# Clock_Schematic_v_2.net
KiCad netlist of a schematic drawn in EAGLE
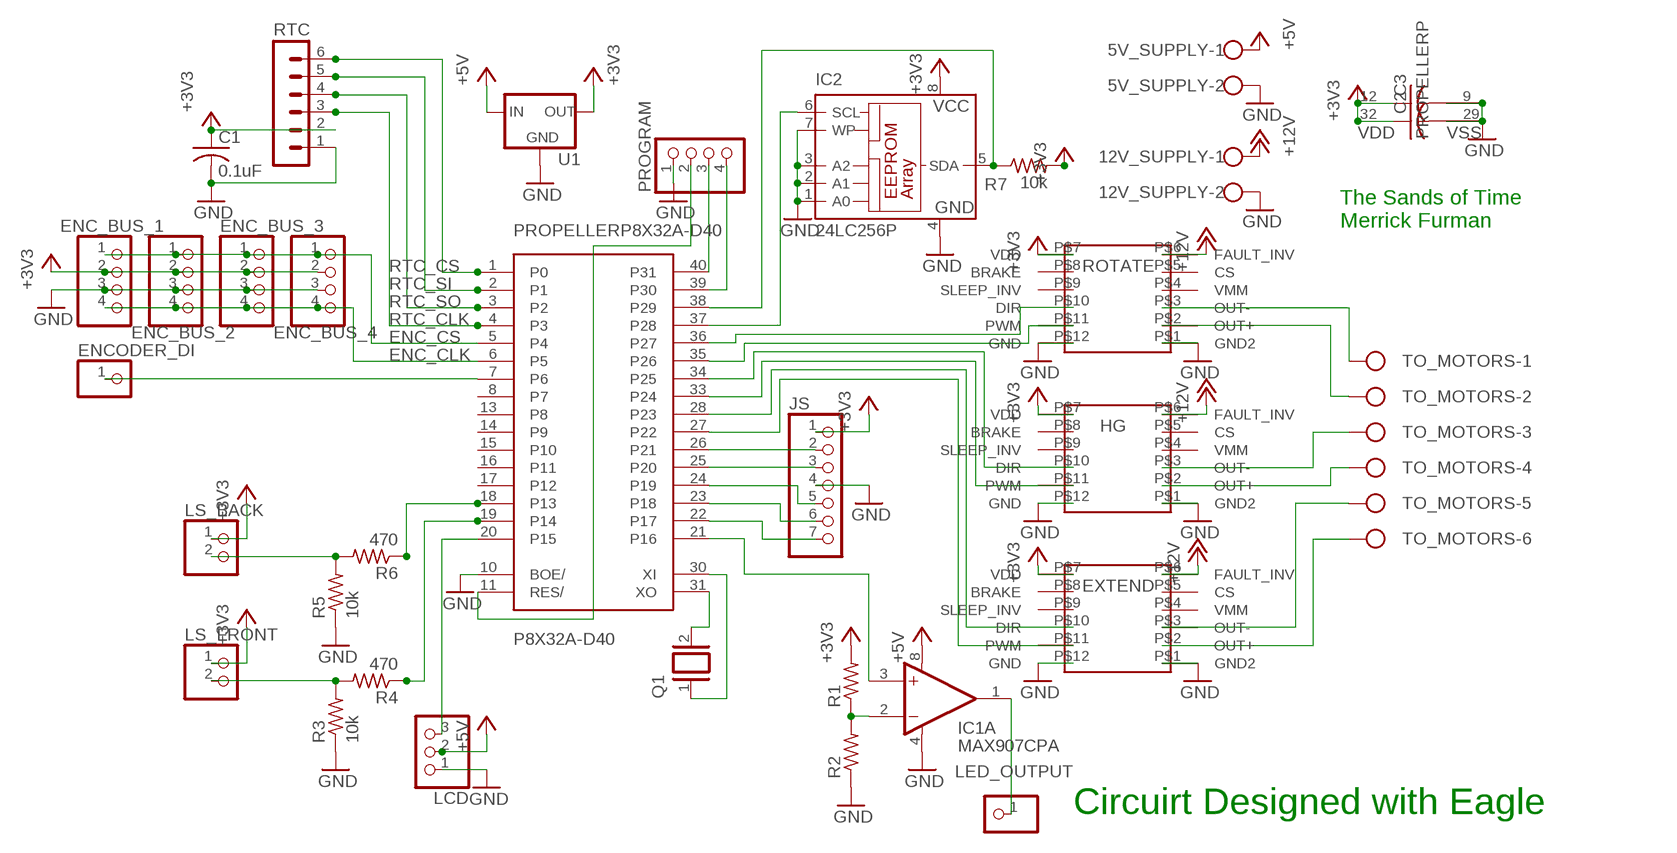
[diagram p0: schematic, sheet 1]

(export (version "E")
  (design (tool "Eeschema 10.0.6"))
  (components
    (comp (ref "5V_SUPPLY")
      (value "W237-102")
      (footprint "eagle-import:W237-102")
      (fields (field (name "MPN") "237-102"))
      (libsource (lib "eagle-import") (part "W237-102"))
    )
    (comp (ref "12V_SUPPLY")
      (value "W237-102")
      (footprint "eagle-import:W237-102")
      (fields (field (name "MPN") "237-102"))
      (libsource (lib "eagle-import") (part "W237-102"))
    )
    (comp (ref "C1")
      (value "0.1uF")
      (footprint "eagle-import:C050-025X075")
      (libsource (lib "eagle-import") (part "C-US050-025X075"))
    )
    (comp (ref "C2")
      (value "C-US050-025X075")
      (footprint "eagle-import:C050-025X075")
      (libsource (lib "eagle-import") (part "C-US050-025X075"))
    )
    (comp (ref "C3")
      (value "C-US050-025X075")
      (footprint "eagle-import:C050-025X075")
      (libsource (lib "eagle-import") (part "C-US050-025X075"))
    )
    (comp (ref "ENCODER_DI")
      (value "PINHD-1X1")
      (footprint "eagle-import:1X01")
      (libsource (lib "eagle-import") (part "PINHD-1X1"))
    )
    (comp (ref "ENC_BUS_1")
      (value "PINHD-1X4")
      (footprint "eagle-import:1X04")
      (libsource (lib "eagle-import") (part "PINHD-1X4"))
    )
    (comp (ref "ENC_BUS_2")
      (value "PINHD-1X4")
      (footprint "eagle-import:1X04")
      (libsource (lib "eagle-import") (part "PINHD-1X4"))
    )
    (comp (ref "ENC_BUS_3")
      (value "PINHD-1X4")
      (footprint "eagle-import:1X04")
      (libsource (lib "eagle-import") (part "PINHD-1X4"))
    )
    (comp (ref "ENC_BUS_4")
      (value "PINHD-1X4")
      (footprint "eagle-import:1X04")
      (libsource (lib "eagle-import") (part "PINHD-1X4"))
    )
    (comp (ref "EXTEND")
      (value "DRV")
      (footprint "eagle-import:DRV")
      (libsource (lib "eagle-import") (part "DRV"))
    )
    (comp (ref "HG")
      (value "DRV")
      (footprint "eagle-import:DRV")
      (libsource (lib "eagle-import") (part "DRV"))
    )
    (comp (ref "IC1")
      (value "MAX907CPA")
      (footprint "eagle-import:DIL08")
      (fields (field (name "MF") "MAXIM"))
      (libsource (lib "eagle-import") (part "MAX907CPA"))
    )
    (comp (ref "IC2")
      (value "24LC256P")
      (footprint "eagle-import:DIL8")
      (fields (field (name "MF") "MICROCHIP") (field (name "MPN") "24LC256-E/P"))
      (libsource (lib "eagle-import") (part "24PLC256"))
    )
    (comp (ref "JS")
      (value "PINHD-1X7")
      (footprint "eagle-import:1X07")
      (libsource (lib "eagle-import") (part "PINHD-1X7"))
    )
    (comp (ref "LCD")
      (value "PINHD-1X3")
      (footprint "eagle-import:1X03")
      (libsource (lib "eagle-import") (part "PINHD-1X3"))
    )
    (comp (ref "LED_OUTPUT")
      (value "PINHD-1X1")
      (footprint "eagle-import:1X01")
      (libsource (lib "eagle-import") (part "PINHD-1X1"))
    )
    (comp (ref "LS_BACK")
      (value "PINHD-1X2")
      (footprint "eagle-import:1X02")
      (libsource (lib "eagle-import") (part "PINHD-1X2"))
    )
    (comp (ref "LS_FRONT")
      (value "PINHD-1X2")
      (footprint "eagle-import:1X02")
      (libsource (lib "eagle-import") (part "PINHD-1X2"))
    )
    (comp (ref "PROGRAM")
      (value "PINHD-1X4")
      (footprint "eagle-import:1X04")
      (libsource (lib "eagle-import") (part "PINHD-1X4"))
    )
    (comp (ref "PROPELLER")
      (value "P8X32A-D40")
      (footprint "eagle-import:P8X32A-D40")
      (libsource (lib "eagle-import") (part "P8X32A-D40"))
    )
    (comp (ref "Q1")
      (value "XTAL/S")
      (footprint "eagle-import:QS")
      (libsource (lib "eagle-import") (part "XTAL/S"))
    )
    (comp (ref "R1")
      (value "R-US_0207/10")
      (footprint "eagle-import:0207_10")
      (libsource (lib "eagle-import") (part "R-US_0207/10"))
    )
    (comp (ref "R2")
      (value "R-US_0207/10")
      (footprint "eagle-import:0207_10")
      (libsource (lib "eagle-import") (part "R-US_0207/10"))
    )
    (comp (ref "R3")
      (value "10k")
      (footprint "eagle-import:0207_10")
      (libsource (lib "eagle-import") (part "R-US_0207/10"))
    )
    (comp (ref "R4")
      (value "470")
      (footprint "eagle-import:0207_10")
      (libsource (lib "eagle-import") (part "R-US_0207/10"))
    )
    (comp (ref "R5")
      (value "10k")
      (footprint "eagle-import:0207_10")
      (libsource (lib "eagle-import") (part "R-US_0207/10"))
    )
    (comp (ref "R6")
      (value "470")
      (footprint "eagle-import:0207_10")
      (libsource (lib "eagle-import") (part "R-US_0207/10"))
    )
    (comp (ref "R7")
      (value "10k")
      (footprint "eagle-import:0207_10")
      (libsource (lib "eagle-import") (part "R-US_0207/10"))
    )
    (comp (ref "ROTATE")
      (value "DRV")
      (footprint "eagle-import:DRV")
      (libsource (lib "eagle-import") (part "DRV"))
    )
    (comp (ref "RTC")
      (value "MA06-1")
      (footprint "eagle-import:MA06-1")
      (libsource (lib "eagle-import") (part "MA06-1"))
    )
    (comp (ref "TO_MOTORS")
      (value "W237-6")
      (footprint "eagle-import:W237-6")
      (libsource (lib "eagle-import") (part "W237-6"))
    )
    (comp (ref "U1")
      (value "V_REG_78XXSIDE")
      (footprint "eagle-import:78XXL")
      (libsource (lib "eagle-import") (part "V_REG_78XXSIDE"))
    )
  )
  (nets
    (net (code "1") (name "+3V3") (class "Default")
      (node (ref "C1") (pin "1") (pinfunction "1_1") (pintype "passive"))
      (node (ref "C2") (pin "1") (pinfunction "1_1") (pintype "passive"))
      (node (ref "C3") (pin "1") (pinfunction "1_1") (pintype "passive"))
      (node (ref "ENC_BUS_1") (pin "2") (pinfunction "2_2") (pintype "passive"))
      (node (ref "ENC_BUS_2") (pin "2") (pinfunction "2_2") (pintype "passive"))
      (node (ref "ENC_BUS_3") (pin "2") (pinfunction "2_2") (pintype "passive"))
      (node (ref "ENC_BUS_4") (pin "2") (pinfunction "2_2") (pintype "passive"))
      (node (ref "EXTEND") (pin "P$7") (pinfunction "VDD_P$7") (pintype "bidirectional"))
      (node (ref "HG") (pin "P$7") (pinfunction "VDD_P$7") (pintype "bidirectional"))
      (node (ref "IC2") (pin "8") (pinfunction "VCC_8") (pintype "power_in"))
      (node (ref "JS") (pin "1") (pinfunction "1_1") (pintype "passive"))
      (node (ref "LS_BACK") (pin "1") (pinfunction "1_1") (pintype "passive"))
      (node (ref "LS_FRONT") (pin "1") (pinfunction "1_1") (pintype "passive"))
      (node (ref "PROPELLER") (pin "12") (pinfunction "VDD_12") (pintype "power_in"))
      (node (ref "PROPELLER") (pin "32") (pinfunction "VDD_32") (pintype "power_in"))
      (node (ref "R1") (pin "2") (pinfunction "2_2") (pintype "passive"))
      (node (ref "R7") (pin "2") (pinfunction "2_2") (pintype "passive"))
      (node (ref "ROTATE") (pin "P$7") (pinfunction "VDD_P$7") (pintype "bidirectional"))
      (node (ref "RTC") (pin "2") (pinfunction "2_2") (pintype "passive"))
      (node (ref "U1") (pin "OUT") (pinfunction "OUT_OUT") (pintype "passive"))
    )
    (net (code "2") (name "+5V") (class "Default")
      (node (ref "5V_SUPPLY") (pin "1") (pinfunction "KL_1") (pintype "passive"))
      (node (ref "IC1") (pin "8") (pinfunction "V+_8") (pintype "power_in"))
      (node (ref "LCD") (pin "2") (pinfunction "2_2") (pintype "passive"))
      (node (ref "U1") (pin "IN") (pinfunction "IN_IN") (pintype "input"))
    )
    (net (code "3") (name "+12V") (class "Default")
      (node (ref "12V_SUPPLY") (pin "1") (pinfunction "KL_1") (pintype "passive"))
      (node (ref "EXTEND") (pin "P$6") (pinfunction "FAULT_INV_P$6") (pintype "bidirectional"))
      (node (ref "HG") (pin "P$6") (pinfunction "FAULT_INV_P$6") (pintype "bidirectional"))
      (node (ref "ROTATE") (pin "P$6") (pinfunction "FAULT_INV_P$6") (pintype "bidirectional"))
    )
    (net (code "4") (name "/ENC_CLK") (class "Default")
      (node (ref "ENC_BUS_1") (pin "4") (pinfunction "4_4") (pintype "passive"))
      (node (ref "ENC_BUS_2") (pin "4") (pinfunction "4_4") (pintype "passive"))
      (node (ref "ENC_BUS_3") (pin "4") (pinfunction "4_4") (pintype "passive"))
      (node (ref "ENC_BUS_4") (pin "4") (pinfunction "4_4") (pintype "passive"))
      (node (ref "PROPELLER") (pin "6") (pinfunction "P5_6") (pintype "bidirectional"))
    )
    (net (code "5") (name "/ENC_CS") (class "Default")
      (node (ref "ENC_BUS_1") (pin "1") (pinfunction "1_1") (pintype "passive"))
      (node (ref "ENC_BUS_2") (pin "1") (pinfunction "1_1") (pintype "passive"))
      (node (ref "ENC_BUS_3") (pin "1") (pinfunction "1_1") (pintype "passive"))
      (node (ref "ENC_BUS_4") (pin "1") (pinfunction "1_1") (pintype "passive"))
      (node (ref "PROPELLER") (pin "5") (pinfunction "P4_5") (pintype "bidirectional"))
    )
    (net (code "6") (name "/RTC_CLK") (class "Default")
      (node (ref "PROPELLER") (pin "4") (pinfunction "P3_4") (pintype "bidirectional"))
      (node (ref "RTC") (pin "3") (pinfunction "3_3") (pintype "passive"))
    )
    (net (code "7") (name "/RTC_CS") (class "Default")
      (node (ref "PROPELLER") (pin "1") (pinfunction "P0_1") (pintype "bidirectional"))
      (node (ref "RTC") (pin "6") (pinfunction "6_6") (pintype "passive"))
    )
    (net (code "8") (name "/RTC_SI") (class "Default")
      (node (ref "PROPELLER") (pin "2") (pinfunction "P1_2") (pintype "bidirectional"))
      (node (ref "RTC") (pin "5") (pinfunction "5_5") (pintype "passive"))
    )
    (net (code "9") (name "/RTC_SO") (class "Default")
      (node (ref "PROPELLER") (pin "3") (pinfunction "P2_3") (pintype "bidirectional"))
      (node (ref "RTC") (pin "4") (pinfunction "4_4") (pintype "passive"))
    )
    (net (code "10") (name "GND") (class "Default")
      (node (ref "12V_SUPPLY") (pin "2") (pinfunction "KL_2") (pintype "passive"))
      (node (ref "5V_SUPPLY") (pin "2") (pinfunction "KL_2") (pintype "passive"))
      (node (ref "C1") (pin "2") (pinfunction "2_2") (pintype "passive"))
      (node (ref "C2") (pin "2") (pinfunction "2_2") (pintype "passive"))
      (node (ref "C3") (pin "2") (pinfunction "2_2") (pintype "passive"))
      (node (ref "ENC_BUS_1") (pin "3") (pinfunction "3_3") (pintype "passive"))
      (node (ref "ENC_BUS_2") (pin "3") (pinfunction "3_3") (pintype "passive"))
      (node (ref "ENC_BUS_3") (pin "3") (pinfunction "3_3") (pintype "passive"))
      (node (ref "ENC_BUS_4") (pin "3") (pinfunction "3_3") (pintype "passive"))
      (node (ref "EXTEND") (pin "P$1") (pinfunction "GND2_P$1") (pintype "bidirectional"))
      (node (ref "EXTEND") (pin "P$12") (pinfunction "GND_P$12") (pintype "bidirectional"))
      (node (ref "HG") (pin "P$1") (pinfunction "GND2_P$1") (pintype "bidirectional"))
      (node (ref "HG") (pin "P$12") (pinfunction "GND_P$12") (pintype "bidirectional"))
      (node (ref "IC1") (pin "4") (pinfunction "V-_4") (pintype "power_in"))
      (node (ref "IC2") (pin "1") (pinfunction "A0_1") (pintype "input"))
      (node (ref "IC2") (pin "2") (pinfunction "A1_2") (pintype "input"))
      (node (ref "IC2") (pin "3") (pinfunction "A2_3") (pintype "input"))
      (node (ref "IC2") (pin "4") (pinfunction "GND_4") (pintype "power_in"))
      (node (ref "IC2") (pin "7") (pinfunction "WP_7") (pintype "input"))
      (node (ref "JS") (pin "4") (pinfunction "4_4") (pintype "passive"))
      (node (ref "LCD") (pin "1") (pinfunction "1_1") (pintype "passive"))
      (node (ref "PROGRAM") (pin "1") (pinfunction "1_1") (pintype "passive"))
      (node (ref "PROPELLER") (pin "10") (pinfunction "BOE/_10") (pintype "input"))
      (node (ref "PROPELLER") (pin "29") (pinfunction "VSS_29") (pintype "power_in"))
      (node (ref "PROPELLER") (pin "9") (pinfunction "VSS_9") (pintype "power_in"))
      (node (ref "R2") (pin "1") (pinfunction "1_1") (pintype "passive"))
      (node (ref "R3") (pin "1") (pinfunction "1_1") (pintype "passive"))
      (node (ref "R5") (pin "1") (pinfunction "1_1") (pintype "passive"))
      (node (ref "ROTATE") (pin "P$1") (pinfunction "GND2_P$1") (pintype "bidirectional"))
      (node (ref "ROTATE") (pin "P$12") (pinfunction "GND_P$12") (pintype "bidirectional"))
      (node (ref "RTC") (pin "1") (pinfunction "1_1") (pintype "passive"))
      (node (ref "U1") (pin "GND") (pinfunction "GND_GND") (pintype "input"))
    )
    (net (code "11") (name "Net-(EXTEND-DIR)") (class "Default")
      (node (ref "EXTEND") (pin "P$10") (pinfunction "DIR_P$10") (pintype "bidirectional"))
      (node (ref "PROPELLER") (pin "28") (pinfunction "P23_28") (pintype "bidirectional"))
    )
    (net (code "12") (name "Net-(EXTEND-OUT+)") (class "Default")
      (node (ref "EXTEND") (pin "P$2") (pinfunction "OUT+_P$2") (pintype "bidirectional"))
      (node (ref "TO_MOTORS") (pin "6") (pinfunction "KL_6") (pintype "passive"))
    )
    (net (code "13") (name "Net-(EXTEND-OUT-)") (class "Default")
      (node (ref "EXTEND") (pin "P$3") (pinfunction "OUT-_P$3") (pintype "bidirectional"))
      (node (ref "TO_MOTORS") (pin "5") (pinfunction "KL_5") (pintype "passive"))
    )
    (net (code "14") (name "Net-(EXTEND-PWM)") (class "Default")
      (node (ref "EXTEND") (pin "P$11") (pinfunction "PWM_P$11") (pintype "bidirectional"))
      (node (ref "PROPELLER") (pin "27") (pinfunction "P22_27") (pintype "bidirectional"))
    )
    (net (code "15") (name "Net-(HG-DIR)") (class "Default")
      (node (ref "HG") (pin "P$10") (pinfunction "DIR_P$10") (pintype "bidirectional"))
      (node (ref "PROPELLER") (pin "34") (pinfunction "P25_34") (pintype "bidirectional"))
    )
    (net (code "16") (name "Net-(HG-OUT+)") (class "Default")
      (node (ref "HG") (pin "P$2") (pinfunction "OUT+_P$2") (pintype "bidirectional"))
      (node (ref "TO_MOTORS") (pin "4") (pinfunction "KL_4") (pintype "passive"))
    )
    (net (code "17") (name "Net-(HG-OUT-)") (class "Default")
      (node (ref "HG") (pin "P$3") (pinfunction "OUT-_P$3") (pintype "bidirectional"))
      (node (ref "TO_MOTORS") (pin "3") (pinfunction "KL_3") (pintype "passive"))
    )
    (net (code "18") (name "Net-(HG-PWM)") (class "Default")
      (node (ref "HG") (pin "P$11") (pinfunction "PWM_P$11") (pintype "bidirectional"))
      (node (ref "PROPELLER") (pin "33") (pinfunction "P24_33") (pintype "bidirectional"))
    )
    (net (code "19") (name "Net-(IC1A-+IN)") (class "Default")
      (node (ref "IC1") (pin "3") (pinfunction "+IN_3") (pintype "input"))
      (node (ref "PROPELLER") (pin "21") (pinfunction "P16_21") (pintype "bidirectional"))
    )
    (net (code "20") (name "Net-(IC1A--IN)") (class "Default")
      (node (ref "IC1") (pin "2") (pinfunction "-IN_2") (pintype "input"))
      (node (ref "R1") (pin "1") (pinfunction "1_1") (pintype "passive"))
      (node (ref "R2") (pin "2") (pinfunction "2_2") (pintype "passive"))
    )
    (net (code "21") (name "Net-(IC1A-OUT)") (class "Default")
      (node (ref "IC1") (pin "1") (pinfunction "OUT_1") (pintype "output"))
      (node (ref "LED_OUTPUT") (pin "1") (pinfunction "1_1") (pintype "passive"))
    )
    (net (code "22") (name "Net-(IC2-SCL)") (class "Default")
      (node (ref "IC2") (pin "6") (pinfunction "SCL_6") (pintype "input"))
      (node (ref "PROPELLER") (pin "37") (pinfunction "P28_37") (pintype "bidirectional"))
    )
    (net (code "23") (name "Net-(IC2-SDA)") (class "Default")
      (node (ref "IC2") (pin "5") (pinfunction "SDA_5") (pintype "bidirectional"))
      (node (ref "PROPELLER") (pin "38") (pinfunction "P29_38") (pintype "bidirectional"))
      (node (ref "R7") (pin "1") (pinfunction "1_1") (pintype "passive"))
    )
    (net (code "24") (name "Net-(LS_BACK-Pad2)") (class "Default")
      (node (ref "LS_BACK") (pin "2") (pinfunction "2_2") (pintype "passive"))
      (node (ref "R5") (pin "2") (pinfunction "2_2") (pintype "passive"))
      (node (ref "R6") (pin "2") (pinfunction "2_2") (pintype "passive"))
    )
    (net (code "25") (name "Net-(LS_FRONT-Pad2)") (class "Default")
      (node (ref "LS_FRONT") (pin "2") (pinfunction "2_2") (pintype "passive"))
      (node (ref "R3") (pin "2") (pinfunction "2_2") (pintype "passive"))
      (node (ref "R4") (pin "2") (pinfunction "2_2") (pintype "passive"))
    )
    (net (code "26") (name "Net-(PROPELLERB-P6)") (class "Default")
      (node (ref "ENCODER_DI") (pin "1") (pinfunction "1_1") (pintype "passive"))
      (node (ref "PROPELLER") (pin "7") (pinfunction "P6_7") (pintype "bidirectional"))
    )
    (net (code "27") (name "Net-(PROPELLERB-P13)") (class "Default")
      (node (ref "PROPELLER") (pin "18") (pinfunction "P13_18") (pintype "bidirectional"))
      (node (ref "R6") (pin "1") (pinfunction "1_1") (pintype "passive"))
    )
    (net (code "28") (name "Net-(PROPELLERB-P14)") (class "Default")
      (node (ref "PROPELLER") (pin "19") (pinfunction "P14_19") (pintype "bidirectional"))
      (node (ref "R4") (pin "1") (pinfunction "1_1") (pintype "passive"))
    )
    (net (code "29") (name "Net-(PROPELLERB-P15)") (class "Default")
      (node (ref "LCD") (pin "3") (pinfunction "3_3") (pintype "passive"))
      (node (ref "PROPELLER") (pin "20") (pinfunction "P15_20") (pintype "bidirectional"))
    )
    (net (code "30") (name "Net-(PROPELLERB-P17)") (class "Default")
      (node (ref "JS") (pin "7") (pinfunction "7_7") (pintype "passive"))
      (node (ref "PROPELLER") (pin "22") (pinfunction "P17_22") (pintype "bidirectional"))
    )
    (net (code "31") (name "Net-(PROPELLERB-P18)") (class "Default")
      (node (ref "JS") (pin "6") (pinfunction "6_6") (pintype "passive"))
      (node (ref "PROPELLER") (pin "23") (pinfunction "P18_23") (pintype "bidirectional"))
    )
    (net (code "32") (name "Net-(PROPELLERB-P19)") (class "Default")
      (node (ref "JS") (pin "5") (pinfunction "5_5") (pintype "passive"))
      (node (ref "PROPELLER") (pin "24") (pinfunction "P19_24") (pintype "bidirectional"))
    )
    (net (code "33") (name "Net-(PROPELLERB-P20)") (class "Default")
      (node (ref "JS") (pin "3") (pinfunction "3_3") (pintype "passive"))
      (node (ref "PROPELLER") (pin "25") (pinfunction "P20_25") (pintype "bidirectional"))
    )
    (net (code "34") (name "Net-(PROPELLERB-P21)") (class "Default")
      (node (ref "JS") (pin "2") (pinfunction "2_2") (pintype "passive"))
      (node (ref "PROPELLER") (pin "26") (pinfunction "P21_26") (pintype "bidirectional"))
    )
    (net (code "35") (name "Net-(PROPELLERB-P26)") (class "Default")
      (node (ref "PROPELLER") (pin "35") (pinfunction "P26_35") (pintype "bidirectional"))
      (node (ref "ROTATE") (pin "P$11") (pinfunction "PWM_P$11") (pintype "bidirectional"))
    )
    (net (code "36") (name "Net-(PROPELLERB-P27)") (class "Default")
      (node (ref "PROPELLER") (pin "36") (pinfunction "P27_36") (pintype "bidirectional"))
      (node (ref "ROTATE") (pin "P$10") (pinfunction "DIR_P$10") (pintype "bidirectional"))
    )
    (net (code "37") (name "Net-(PROPELLERB-P30)") (class "Default")
      (node (ref "PROGRAM") (pin "4") (pinfunction "4_4") (pintype "passive"))
      (node (ref "PROPELLER") (pin "39") (pinfunction "P30_39") (pintype "bidirectional"))
    )
    (net (code "38") (name "Net-(PROPELLERB-P31)") (class "Default")
      (node (ref "PROGRAM") (pin "3") (pinfunction "3_3") (pintype "passive"))
      (node (ref "PROPELLER") (pin "40") (pinfunction "P31_40") (pintype "bidirectional"))
    )
    (net (code "39") (name "Net-(PROPELLERB-RES{slash})") (class "Default")
      (node (ref "PROGRAM") (pin "2") (pinfunction "2_2") (pintype "passive"))
      (node (ref "PROPELLER") (pin "11") (pinfunction "RES/_11") (pintype "bidirectional"))
    )
    (net (code "40") (name "Net-(PROPELLERB-XI)") (class "Default")
      (node (ref "PROPELLER") (pin "30") (pinfunction "XI_30") (pintype "input"))
      (node (ref "Q1") (pin "1") (pinfunction "1_1") (pintype "passive"))
    )
    (net (code "41") (name "Net-(PROPELLERB-XO)") (class "Default")
      (node (ref "PROPELLER") (pin "31") (pinfunction "XO_31") (pintype "output"))
      (node (ref "Q1") (pin "2") (pinfunction "2_2") (pintype "passive"))
    )
    (net (code "42") (name "Net-(ROTATE-OUT+)") (class "Default")
      (node (ref "ROTATE") (pin "P$2") (pinfunction "OUT+_P$2") (pintype "bidirectional"))
      (node (ref "TO_MOTORS") (pin "2") (pinfunction "KL_2") (pintype "passive"))
    )
    (net (code "43") (name "Net-(ROTATE-OUT-)") (class "Default")
      (node (ref "ROTATE") (pin "P$3") (pinfunction "OUT-_P$3") (pintype "bidirectional"))
      (node (ref "TO_MOTORS") (pin "1") (pinfunction "KL_1") (pintype "passive"))
    )
    (net (code "44") (name "unconnected-(EXTEND-BRAKE-PadP$8)") (class "Default")
      (node (ref "EXTEND") (pin "P$8") (pinfunction "BRAKE_P$8") (pintype "bidirectional"))
    )
    (net (code "45") (name "unconnected-(EXTEND-CS-PadP$5)") (class "Default")
      (node (ref "EXTEND") (pin "P$5") (pinfunction "CS_P$5") (pintype "bidirectional"))
    )
    (net (code "46") (name "unconnected-(EXTEND-SLEEP_INV-PadP$9)") (class "Default")
      (node (ref "EXTEND") (pin "P$9") (pinfunction "SLEEP_INV_P$9") (pintype "bidirectional"))
    )
    (net (code "47") (name "unconnected-(EXTEND-VMM-PadP$4)") (class "Default")
      (node (ref "EXTEND") (pin "P$4") (pinfunction "VMM_P$4") (pintype "bidirectional"))
    )
    (net (code "48") (name "unconnected-(HG-BRAKE-PadP$8)") (class "Default")
      (node (ref "HG") (pin "P$8") (pinfunction "BRAKE_P$8") (pintype "bidirectional"))
    )
    (net (code "49") (name "unconnected-(HG-CS-PadP$5)") (class "Default")
      (node (ref "HG") (pin "P$5") (pinfunction "CS_P$5") (pintype "bidirectional"))
    )
    (net (code "50") (name "unconnected-(HG-SLEEP_INV-PadP$9)") (class "Default")
      (node (ref "HG") (pin "P$9") (pinfunction "SLEEP_INV_P$9") (pintype "bidirectional"))
    )
    (net (code "51") (name "unconnected-(HG-VMM-PadP$4)") (class "Default")
      (node (ref "HG") (pin "P$4") (pinfunction "VMM_P$4") (pintype "bidirectional"))
    )
    (net (code "52") (name "unconnected-(PROPELLERB-P7-Pad8)") (class "Default")
      (node (ref "PROPELLER") (pin "8") (pinfunction "P7_8") (pintype "bidirectional"))
    )
    (net (code "53") (name "unconnected-(PROPELLERB-P8-Pad13)") (class "Default")
      (node (ref "PROPELLER") (pin "13") (pinfunction "P8_13") (pintype "bidirectional"))
    )
    (net (code "54") (name "unconnected-(PROPELLERB-P9-Pad14)") (class "Default")
      (node (ref "PROPELLER") (pin "14") (pinfunction "P9_14") (pintype "bidirectional"))
    )
    (net (code "55") (name "unconnected-(PROPELLERB-P10-Pad15)") (class "Default")
      (node (ref "PROPELLER") (pin "15") (pinfunction "P10_15") (pintype "bidirectional"))
    )
    (net (code "56") (name "unconnected-(PROPELLERB-P11-Pad16)") (class "Default")
      (node (ref "PROPELLER") (pin "16") (pinfunction "P11_16") (pintype "bidirectional"))
    )
    (net (code "57") (name "unconnected-(PROPELLERB-P12-Pad17)") (class "Default")
      (node (ref "PROPELLER") (pin "17") (pinfunction "P12_17") (pintype "bidirectional"))
    )
    (net (code "58") (name "unconnected-(ROTATE-BRAKE-PadP$8)") (class "Default")
      (node (ref "ROTATE") (pin "P$8") (pinfunction "BRAKE_P$8") (pintype "bidirectional"))
    )
    (net (code "59") (name "unconnected-(ROTATE-CS-PadP$5)") (class "Default")
      (node (ref "ROTATE") (pin "P$5") (pinfunction "CS_P$5") (pintype "bidirectional"))
    )
    (net (code "60") (name "unconnected-(ROTATE-SLEEP_INV-PadP$9)") (class "Default")
      (node (ref "ROTATE") (pin "P$9") (pinfunction "SLEEP_INV_P$9") (pintype "bidirectional"))
    )
    (net (code "61") (name "unconnected-(ROTATE-VMM-PadP$4)") (class "Default")
      (node (ref "ROTATE") (pin "P$4") (pinfunction "VMM_P$4") (pintype "bidirectional"))
    )
  )
)
